# ldr.net
KiCad netlist of a schematic drawn in EAGLE
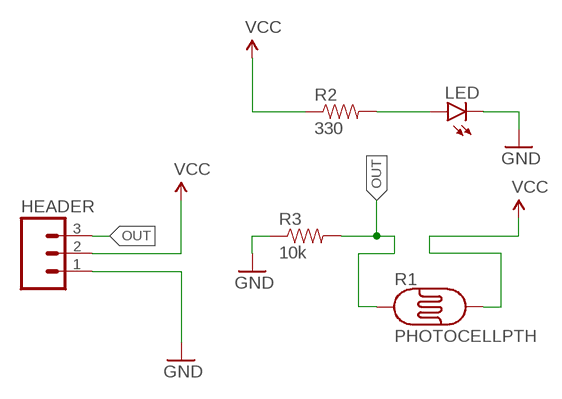
[diagram p0: schematic, sheet 1]

(export (version "E")
  (design (tool "Eeschema 10.0.6"))
  (components
    (comp (ref "HEADER")
      (value "M03PTH")
      (footprint "eagle-import:1X03")
      (libsource (lib "eagle-import") (part "M03PTH"))
    )
    (comp (ref "LED")
      (value "LED5MM")
      (footprint "eagle-import:LED5MM")
      (libsource (lib "eagle-import") (part "LED5MM"))
    )
    (comp (ref "R1")
      (value "PHOTOCELLPTH")
      (footprint "eagle-import:PHOTOCELL")
      (libsource (lib "eagle-import") (part "PHOTOCELLPTH"))
    )
    (comp (ref "R2")
      (value "330")
      (footprint "eagle-import:AXIAL-0.3EZ")
      (libsource (lib "eagle-import") (part "RESISTOREZ"))
    )
    (comp (ref "R3")
      (value "10k")
      (footprint "eagle-import:AXIAL-0.3EZ")
      (libsource (lib "eagle-import") (part "RESISTOREZ"))
    )
  )
  (nets
    (net (code "1") (name "GND") (class "Default")
      (node (ref "HEADER") (pin "1") (pinfunction "1_1") (pintype "passive"))
      (node (ref "LED") (pin "K") (pinfunction "C_K") (pintype "passive"))
      (node (ref "R3") (pin "P$1") (pinfunction "1_P$1") (pintype "passive"))
    )
    (net (code "2") (name "Net-(R2-2)") (class "Default")
      (node (ref "LED") (pin "A") (pinfunction "A_A") (pintype "passive"))
      (node (ref "R2") (pin "P$2") (pinfunction "2_P$2") (pintype "passive"))
    )
    (net (code "3") (name "OUT") (class "Default")
      (node (ref "HEADER") (pin "3") (pinfunction "3_3") (pintype "passive"))
      (node (ref "R1") (pin "1") (pinfunction "P$1_1") (pintype "bidirectional"))
      (node (ref "R3") (pin "P$2") (pinfunction "2_P$2") (pintype "passive"))
    )
    (net (code "4") (name "VCC") (class "Default")
      (node (ref "HEADER") (pin "2") (pinfunction "2_2") (pintype "passive"))
      (node (ref "R1") (pin "2") (pinfunction "P$2_2") (pintype "bidirectional"))
      (node (ref "R2") (pin "P$1") (pinfunction "1_P$1") (pintype "passive"))
    )
  )
)
